# CC1101-1190EM_Adapter_V3_00.net
KiCad netlist of a schematic drawn in EAGLE
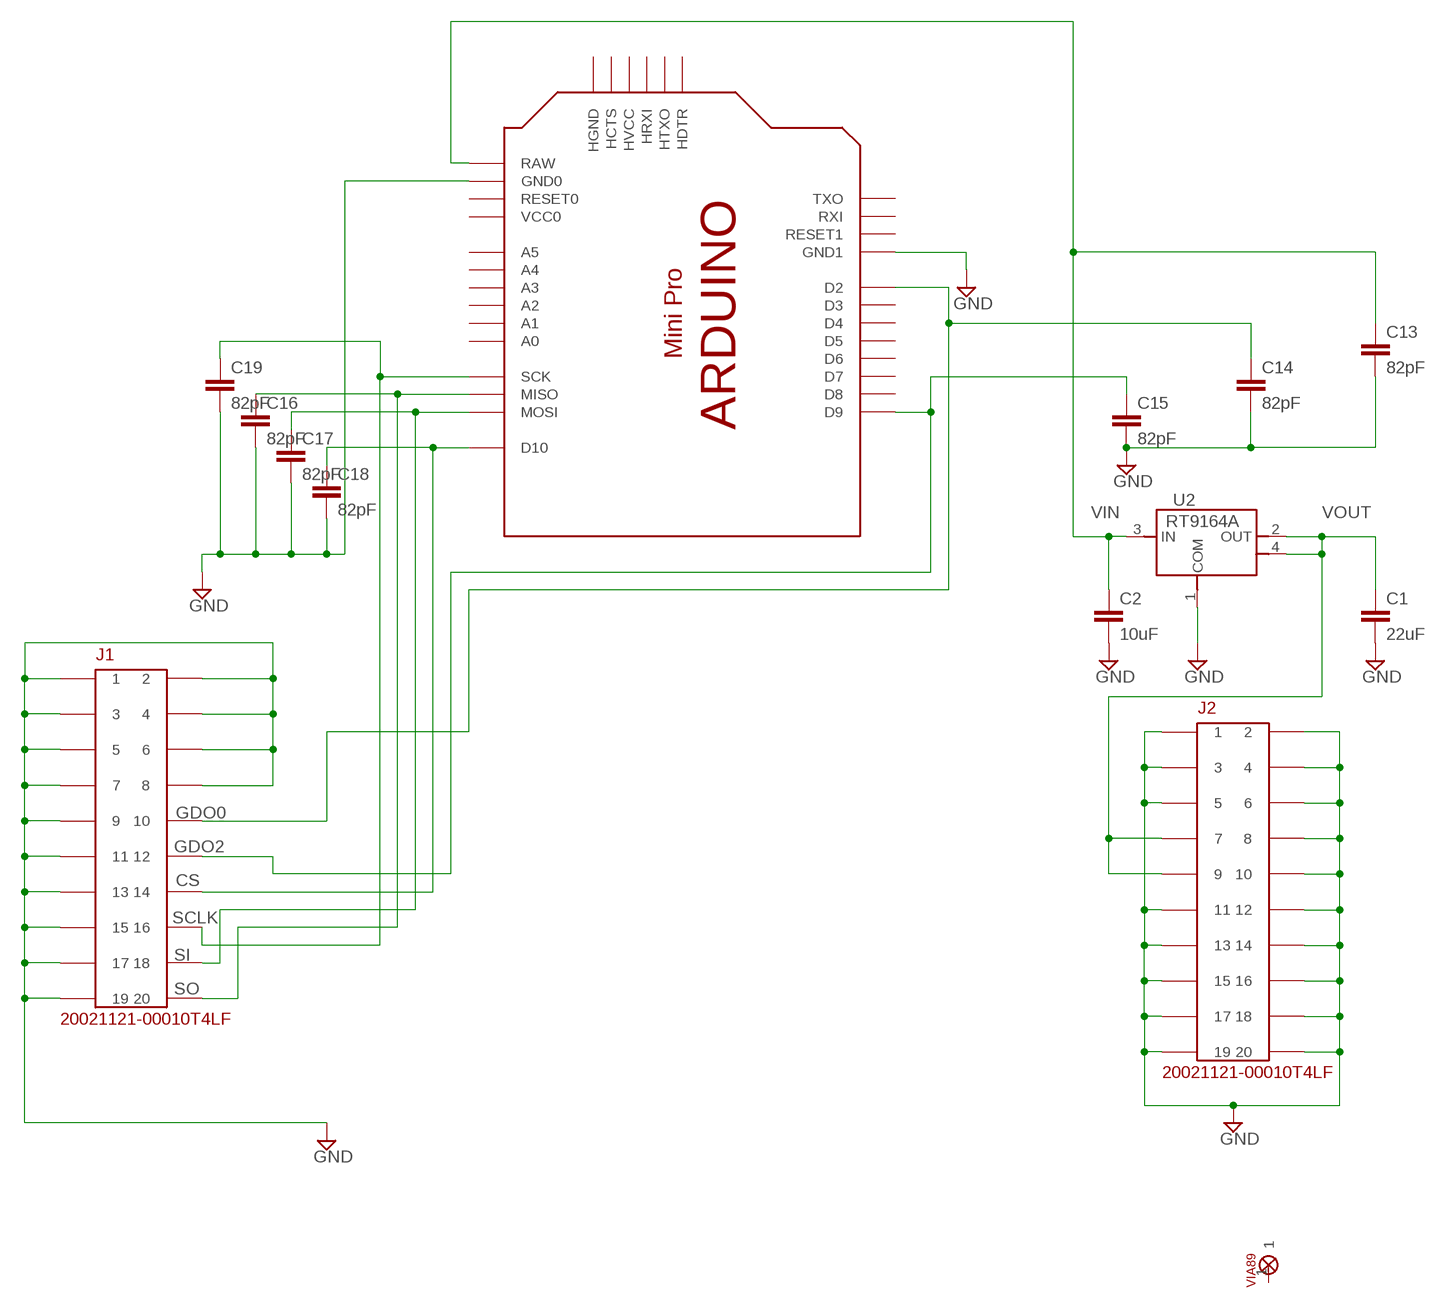
[diagram p0: schematic, sheet 1]

(export (version "E")
  (design (tool "Eeschema 10.0.6"))
  (components
    (comp (ref "C1")
      (value "22uF")
      (footprint "eagle-import:C1206")
      (libsource (lib "eagle-import") (part "CC1206"))
    )
    (comp (ref "C2")
      (value "10uF")
      (footprint "eagle-import:C1206")
      (libsource (lib "eagle-import") (part "CC1206"))
    )
    (comp (ref "C13")
      (value "82pF")
      (footprint "eagle-import:C0805")
      (libsource (lib "eagle-import") (part "C"))
    )
    (comp (ref "C14")
      (value "82pF")
      (footprint "eagle-import:C0805")
      (libsource (lib "eagle-import") (part "C"))
    )
    (comp (ref "C15")
      (value "82pF")
      (footprint "eagle-import:C0805")
      (libsource (lib "eagle-import") (part "C"))
    )
    (comp (ref "C16")
      (value "82pF")
      (footprint "eagle-import:C0805")
      (libsource (lib "eagle-import") (part "C"))
    )
    (comp (ref "C17")
      (value "82pF")
      (footprint "eagle-import:C0805")
      (libsource (lib "eagle-import") (part "C"))
    )
    (comp (ref "C18")
      (value "82pF")
      (footprint "eagle-import:C0805")
      (libsource (lib "eagle-import") (part "C"))
    )
    (comp (ref "C19")
      (value "82pF")
      (footprint "eagle-import:C0805")
      (libsource (lib "eagle-import") (part "C"))
    )
    (comp (ref "J1")
      (value "20021121-00010T4LF")
      (footprint "eagle-import:PINHDR10X2_50X50MIL_SMT")
      (libsource (lib "eagle-import") (part "20021121-00010T4LF"))
    )
    (comp (ref "J2")
      (value "20021121-00010T4LF")
      (footprint "eagle-import:PINHDR10X2_50X50MIL_SMT")
      (libsource (lib "eagle-import") (part "20021121-00010T4LF"))
    )
    (comp (ref "U$1")
      (value "ARDUINOMINI")
      (footprint "eagle-import:ARDUINOMINI")
      (libsource (lib "eagle-import") (part "ARDUINOMINI"))
    )
    (comp (ref "U2")
      (value "RT9164A")
      (footprint "eagle-import:TO223")
      (libsource (lib "eagle-import") (part "RT9164A"))
    )
    (comp (ref "VIA89")
      (value "GND_VIA_NO_THERMAL")
      (footprint "eagle-import:VIA_NO_THERMAL")
      (libsource (lib "eagle-import") (part "GND_VIA_NO_THERMAL"))
    )
  )
  (nets
    (net (code "1") (name "/CS") (class "Default")
      (node (ref "C18") (pin "1") (pinfunction "1_1") (pintype "passive"))
      (node (ref "J1") (pin "P$14") (pinfunction "14_P$14") (pintype "bidirectional"))
      (node (ref "U$1") (pin "P$30") (pinfunction "D10_P$30") (pintype "bidirectional"))
    )
    (net (code "2") (name "/GDO0") (class "Default")
      (node (ref "C14") (pin "1") (pinfunction "1_1") (pintype "passive"))
      (node (ref "J1") (pin "P$10") (pinfunction "10_P$10") (pintype "bidirectional"))
      (node (ref "U$1") (pin "P$8") (pinfunction "D2_P$8") (pintype "bidirectional"))
    )
    (net (code "3") (name "/GDO2") (class "Default")
      (node (ref "C15") (pin "1") (pinfunction "1_1") (pintype "passive"))
      (node (ref "J1") (pin "P$12") (pinfunction "12_P$12") (pintype "bidirectional"))
      (node (ref "U$1") (pin "P$1") (pinfunction "D9_P$1") (pintype "bidirectional"))
    )
    (net (code "4") (name "/SCLK") (class "Default")
      (node (ref "C19") (pin "1") (pinfunction "1_1") (pintype "passive"))
      (node (ref "J1") (pin "P$16") (pinfunction "16_P$16") (pintype "bidirectional"))
      (node (ref "U$1") (pin "P$27") (pinfunction "SCK_P$27") (pintype "bidirectional"))
    )
    (net (code "5") (name "/SI") (class "Default")
      (node (ref "C17") (pin "1") (pinfunction "1_1") (pintype "passive"))
      (node (ref "J1") (pin "P$18") (pinfunction "18_P$18") (pintype "bidirectional"))
      (node (ref "U$1") (pin "P$29") (pinfunction "MOSI_P$29") (pintype "bidirectional"))
    )
    (net (code "6") (name "/SO") (class "Default")
      (node (ref "C16") (pin "1") (pinfunction "1_1") (pintype "passive"))
      (node (ref "J1") (pin "P$20") (pinfunction "20_P$20") (pintype "bidirectional"))
      (node (ref "U$1") (pin "P$28") (pinfunction "MISO_P$28") (pintype "bidirectional"))
    )
    (net (code "7") (name "/VIN") (class "Default")
      (node (ref "C13") (pin "1") (pinfunction "1_1") (pintype "passive"))
      (node (ref "C2") (pin "1") (pinfunction "1_1") (pintype "passive"))
      (node (ref "U$1") (pin "P$19") (pinfunction "RAW_P$19") (pintype "bidirectional"))
      (node (ref "U2") (pin "3") (pinfunction "IN_3") (pintype "input"))
    )
    (net (code "8") (name "/VOUT") (class "Default")
      (node (ref "C1") (pin "1") (pinfunction "1_1") (pintype "passive"))
      (node (ref "J2") (pin "P$7") (pinfunction "7_P$7") (pintype "bidirectional"))
      (node (ref "J2") (pin "P$9") (pinfunction "9_P$9") (pintype "bidirectional"))
      (node (ref "U2") (pin "2") (pinfunction "OUT_2") (pintype "passive"))
      (node (ref "U2") (pin "4") (pinfunction "OUT_4") (pintype "passive"))
    )
    (net (code "9") (name "GND") (class "Default")
      (node (ref "C1") (pin "2") (pinfunction "2_2") (pintype "passive"))
      (node (ref "C13") (pin "2") (pinfunction "2_2") (pintype "passive"))
      (node (ref "C14") (pin "2") (pinfunction "2_2") (pintype "passive"))
      (node (ref "C15") (pin "2") (pinfunction "2_2") (pintype "passive"))
      (node (ref "C16") (pin "2") (pinfunction "2_2") (pintype "passive"))
      (node (ref "C17") (pin "2") (pinfunction "2_2") (pintype "passive"))
      (node (ref "C18") (pin "2") (pinfunction "2_2") (pintype "passive"))
      (node (ref "C19") (pin "2") (pinfunction "2_2") (pintype "passive"))
      (node (ref "C2") (pin "2") (pinfunction "2_2") (pintype "passive"))
      (node (ref "J1") (pin "P$1") (pinfunction "1_P$1") (pintype "bidirectional"))
      (node (ref "J1") (pin "P$11") (pinfunction "11_P$11") (pintype "bidirectional"))
      (node (ref "J1") (pin "P$13") (pinfunction "13_P$13") (pintype "bidirectional"))
      (node (ref "J1") (pin "P$15") (pinfunction "15_P$15") (pintype "bidirectional"))
      (node (ref "J1") (pin "P$17") (pinfunction "17_P$17") (pintype "bidirectional"))
      (node (ref "J1") (pin "P$19") (pinfunction "19_P$19") (pintype "bidirectional"))
      (node (ref "J1") (pin "P$2") (pinfunction "2_P$2") (pintype "bidirectional"))
      (node (ref "J1") (pin "P$3") (pinfunction "3_P$3") (pintype "bidirectional"))
      (node (ref "J1") (pin "P$4") (pinfunction "4_P$4") (pintype "bidirectional"))
      (node (ref "J1") (pin "P$5") (pinfunction "5_P$5") (pintype "bidirectional"))
      (node (ref "J1") (pin "P$6") (pinfunction "6_P$6") (pintype "bidirectional"))
      (node (ref "J1") (pin "P$7") (pinfunction "7_P$7") (pintype "bidirectional"))
      (node (ref "J1") (pin "P$8") (pinfunction "8_P$8") (pintype "bidirectional"))
      (node (ref "J1") (pin "P$9") (pinfunction "9_P$9") (pintype "bidirectional"))
      (node (ref "J2") (pin "P$1") (pinfunction "1_P$1") (pintype "bidirectional"))
      (node (ref "J2") (pin "P$10") (pinfunction "10_P$10") (pintype "bidirectional"))
      (node (ref "J2") (pin "P$11") (pinfunction "11_P$11") (pintype "bidirectional"))
      (node (ref "J2") (pin "P$12") (pinfunction "12_P$12") (pintype "bidirectional"))
      (node (ref "J2") (pin "P$13") (pinfunction "13_P$13") (pintype "bidirectional"))
      (node (ref "J2") (pin "P$14") (pinfunction "14_P$14") (pintype "bidirectional"))
      (node (ref "J2") (pin "P$15") (pinfunction "15_P$15") (pintype "bidirectional"))
      (node (ref "J2") (pin "P$16") (pinfunction "16_P$16") (pintype "bidirectional"))
      (node (ref "J2") (pin "P$17") (pinfunction "17_P$17") (pintype "bidirectional"))
      (node (ref "J2") (pin "P$18") (pinfunction "18_P$18") (pintype "bidirectional"))
      (node (ref "J2") (pin "P$19") (pinfunction "19_P$19") (pintype "bidirectional"))
      (node (ref "J2") (pin "P$2") (pinfunction "2_P$2") (pintype "bidirectional"))
      (node (ref "J2") (pin "P$20") (pinfunction "20_P$20") (pintype "bidirectional"))
      (node (ref "J2") (pin "P$3") (pinfunction "3_P$3") (pintype "bidirectional"))
      (node (ref "J2") (pin "P$4") (pinfunction "4_P$4") (pintype "bidirectional"))
      (node (ref "J2") (pin "P$5") (pinfunction "5_P$5") (pintype "bidirectional"))
      (node (ref "J2") (pin "P$6") (pinfunction "6_P$6") (pintype "bidirectional"))
      (node (ref "J2") (pin "P$8") (pinfunction "8_P$8") (pintype "bidirectional"))
      (node (ref "U$1") (pin "P$20") (pinfunction "GND0_P$20") (pintype "bidirectional"))
      (node (ref "U$1") (pin "P$9") (pinfunction "GND1_P$9") (pintype "bidirectional"))
      (node (ref "U2") (pin "1") (pinfunction "COM_1") (pintype "input"))
    )
    (net (code "10") (name "unconnected-(U$1-A0-PadP$26)") (class "Default")
      (node (ref "U$1") (pin "P$26") (pinfunction "A0_P$26") (pintype "bidirectional"))
    )
    (net (code "11") (name "unconnected-(U$1-A1-PadP$25)") (class "Default")
      (node (ref "U$1") (pin "P$25") (pinfunction "A1_P$25") (pintype "bidirectional"))
    )
    (net (code "12") (name "unconnected-(U$1-A2-PadP$24)") (class "Default")
      (node (ref "U$1") (pin "P$24") (pinfunction "A2_P$24") (pintype "bidirectional"))
    )
    (net (code "13") (name "unconnected-(U$1-A3-PadP$23)") (class "Default")
      (node (ref "U$1") (pin "P$23") (pinfunction "A3_P$23") (pintype "bidirectional"))
    )
    (net (code "14") (name "unconnected-(U$1-A4-PadP$34)") (class "Default")
      (node (ref "U$1") (pin "P$34") (pinfunction "A4_P$34") (pintype "bidirectional"))
    )
    (net (code "15") (name "unconnected-(U$1-A5-PadP$35)") (class "Default")
      (node (ref "U$1") (pin "P$35") (pinfunction "A5_P$35") (pintype "bidirectional"))
    )
    (net (code "16") (name "unconnected-(U$1-D3-PadP$7)") (class "Default")
      (node (ref "U$1") (pin "P$7") (pinfunction "D3_P$7") (pintype "bidirectional"))
    )
    (net (code "17") (name "unconnected-(U$1-D4-PadP$6)") (class "Default")
      (node (ref "U$1") (pin "P$6") (pinfunction "D4_P$6") (pintype "bidirectional"))
    )
    (net (code "18") (name "unconnected-(U$1-D5-PadP$5)") (class "Default")
      (node (ref "U$1") (pin "P$5") (pinfunction "D5_P$5") (pintype "bidirectional"))
    )
    (net (code "19") (name "unconnected-(U$1-D6-PadP$4)") (class "Default")
      (node (ref "U$1") (pin "P$4") (pinfunction "D6_P$4") (pintype "bidirectional"))
    )
    (net (code "20") (name "unconnected-(U$1-D7-PadP$3)") (class "Default")
      (node (ref "U$1") (pin "P$3") (pinfunction "D7_P$3") (pintype "bidirectional"))
    )
    (net (code "21") (name "unconnected-(U$1-D8-PadP$2)") (class "Default")
      (node (ref "U$1") (pin "P$2") (pinfunction "D8_P$2") (pintype "bidirectional"))
    )
    (net (code "22") (name "unconnected-(U$1-HCTS-PadP$17)") (class "Default")
      (node (ref "U$1") (pin "P$17") (pinfunction "HCTS_P$17") (pintype "bidirectional"))
    )
    (net (code "23") (name "unconnected-(U$1-HDTR-PadP$13)") (class "Default")
      (node (ref "U$1") (pin "P$13") (pinfunction "HDTR_P$13") (pintype "bidirectional"))
    )
    (net (code "24") (name "unconnected-(U$1-HGND-PadP$18)") (class "Default")
      (node (ref "U$1") (pin "P$18") (pinfunction "HGND_P$18") (pintype "bidirectional"))
    )
    (net (code "25") (name "unconnected-(U$1-HRXI-PadP$15)") (class "Default")
      (node (ref "U$1") (pin "P$15") (pinfunction "HRXI_P$15") (pintype "bidirectional"))
    )
    (net (code "26") (name "unconnected-(U$1-HTXO-PadP$14)") (class "Default")
      (node (ref "U$1") (pin "P$14") (pinfunction "HTXO_P$14") (pintype "bidirectional"))
    )
    (net (code "27") (name "unconnected-(U$1-HVCC-PadP$16)") (class "Default")
      (node (ref "U$1") (pin "P$16") (pinfunction "HVCC_P$16") (pintype "bidirectional"))
    )
    (net (code "28") (name "unconnected-(U$1-RESET0-PadP$21)") (class "Default")
      (node (ref "U$1") (pin "P$21") (pinfunction "RESET0_P$21") (pintype "bidirectional"))
    )
    (net (code "29") (name "unconnected-(U$1-RESET1-PadP$10)") (class "Default")
      (node (ref "U$1") (pin "P$10") (pinfunction "RESET1_P$10") (pintype "bidirectional"))
    )
    (net (code "30") (name "unconnected-(U$1-RXI-PadP$11)") (class "Default")
      (node (ref "U$1") (pin "P$11") (pinfunction "RXI_P$11") (pintype "bidirectional"))
    )
    (net (code "31") (name "unconnected-(U$1-TXO-PadP$12)") (class "Default")
      (node (ref "U$1") (pin "P$12") (pinfunction "TXO_P$12") (pintype "bidirectional"))
    )
    (net (code "32") (name "unconnected-(U$1-VCC0-PadP$22)") (class "Default")
      (node (ref "U$1") (pin "P$22") (pinfunction "VCC0_P$22") (pintype "bidirectional"))
    )
    (net (code "33") (name "unconnected-(VIA89-Pad1)") (class "Default")
      (node (ref "VIA89") (pin "1") (pinfunction "1_1") (pintype "bidirectional"))
    )
  )
)
